# Telescope_Interface_shield.net
KiCad netlist of a schematic drawn in EAGLE
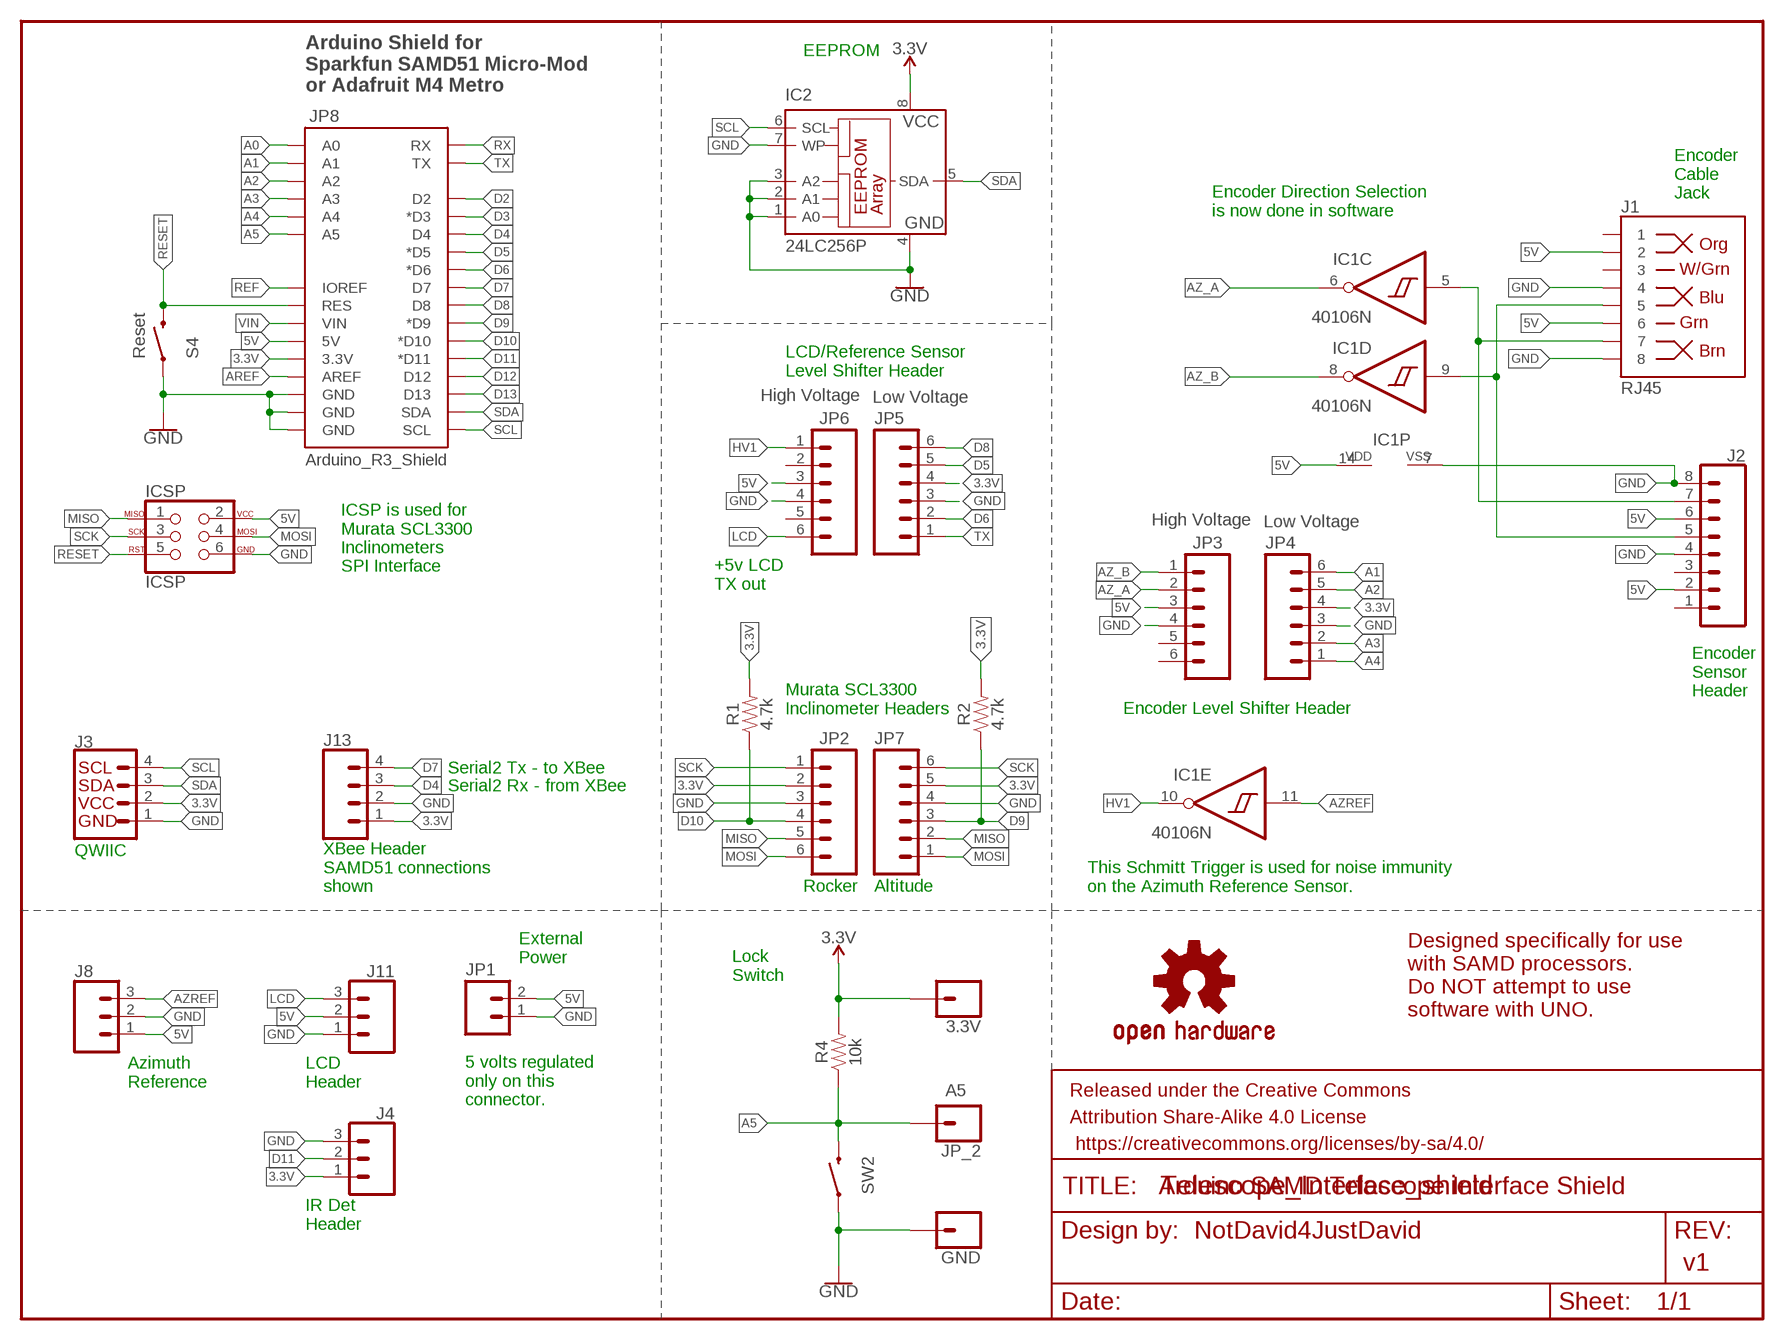
[diagram p0: schematic, sheet 1]

(export (version "E")
  (design (tool "Eeschema 10.0.6"))
  (components
    (comp (ref "3.3V")
      (value "CONN_01")
      (footprint "eagle-import:1X01")
      (libsource (lib "eagle-import") (part "CONN_01"))
    )
    (comp (ref "FRAME1")
      (value "FRAME-LETTER")
      (footprint "eagle-import:CREATIVE_COMMONS")
      (fields (field (name "DESIGNER") "NotDavid4JustDavid") (field (name "REV") "v1"))
      (libsource (lib "eagle-import") (part "FRAME-LETTER"))
    )
    (comp (ref "GND")
      (value "CONN_01")
      (footprint "eagle-import:1X01")
      (libsource (lib "eagle-import") (part "CONN_01"))
    )
    (comp (ref "IC1")
      (value "40106N")
      (footprint "eagle-import:DIL14")
      (libsource (lib "eagle-import") (part "40106N"))
    )
    (comp (ref "IC2")
      (value "24LC256P")
      (footprint "eagle-import:DIL8")
      (fields (field (name "MF") "MICROCHIP") (field (name "MPN") "24LC256-E/P"))
      (libsource (lib "eagle-import") (part "24PLC256"))
    )
    (comp (ref "ICSP")
      (value "ICSP")
      (footprint "eagle-import:2X3")
      (libsource (lib "eagle-import") (part "AVR_SPI_PROG_3X2PTH"))
    )
    (comp (ref "J1")
      (value "RJ45")
      (footprint "eagle-import:RJ45-8")
      (libsource (lib "eagle-import") (part "RJ45-8"))
    )
    (comp (ref "J2")
      (value "CONN_08\"")
      (footprint "eagle-import:1X08")
      (libsource (lib "eagle-import") (part "CONN_08{dblquote}"))
    )
    (comp (ref "J3")
      (value "QWIIC_CONNECTORJS-1MM")
      (footprint "eagle-import:JST04_1MM_RA")
      (libsource (lib "eagle-import") (part "QWIIC_CONNECTORJS-1MM"))
    )
    (comp (ref "J4")
      (value "455-1750-1-ND")
      (footprint "eagle-import:1X03")
      (libsource (lib "eagle-import") (part "CONN_03"))
    )
    (comp (ref "J8")
      (value "455-1750-1-ND")
      (footprint "eagle-import:1X03")
      (libsource (lib "eagle-import") (part "CONN_03"))
    )
    (comp (ref "J11")
      (value "455-1750-1-ND")
      (footprint "eagle-import:1X03")
      (libsource (lib "eagle-import") (part "CONN_03"))
    )
    (comp (ref "J13")
      (value "CONN_04PTH")
      (footprint "eagle-import:1X04")
      (libsource (lib "eagle-import") (part "CONN_04PTH"))
    )
    (comp (ref "JP1")
      (value "CONN_02JST-PTH-2")
      (footprint "eagle-import:JST-2-PTH")
      (libsource (lib "eagle-import") (part "CONN_02JST-PTH-2"))
    )
    (comp (ref "JP2")
      (value "M06SIP")
      (footprint "eagle-import:1X06")
      (libsource (lib "eagle-import") (part "M06SIP"))
    )
    (comp (ref "JP3")
      (value "M06SIP")
      (footprint "eagle-import:1X06")
      (libsource (lib "eagle-import") (part "M06SIP"))
    )
    (comp (ref "JP4")
      (value "M06SIP")
      (footprint "eagle-import:1X06")
      (libsource (lib "eagle-import") (part "M06SIP"))
    )
    (comp (ref "JP5")
      (value "M06SIP")
      (footprint "eagle-import:1X06")
      (libsource (lib "eagle-import") (part "M06SIP"))
    )
    (comp (ref "JP6")
      (value "M06SIP")
      (footprint "eagle-import:1X06")
      (libsource (lib "eagle-import") (part "M06SIP"))
    )
    (comp (ref "JP7")
      (value "M06SIP")
      (footprint "eagle-import:1X06")
      (libsource (lib "eagle-import") (part "M06SIP"))
    )
    (comp (ref "JP8")
      (value "ARDUINO_R3_SHIELDR3_PROTO_SHIELD")
      (footprint "eagle-import:UNO_R3_PROTO_SHIELD")
      (libsource (lib "eagle-import") (part "ARDUINO_R3_SHIELDR3_PROTO_SHIELD"))
    )
    (comp (ref "JP_2")
      (value "CONN_01")
      (footprint "eagle-import:1X01")
      (libsource (lib "eagle-import") (part "CONN_01"))
    )
    (comp (ref "LOGO1")
      (value "OSHW-LOGOS")
      (footprint "eagle-import:OSHW-LOGO-S")
      (libsource (lib "eagle-import") (part "OSHW-LOGOS"))
    )
    (comp (ref "R1")
      (value "4.7k")
      (footprint "eagle-import:0603")
      (libsource (lib "eagle-import") (part "4.7KOHM-0603-1/10W-1%"))
    )
    (comp (ref "R2")
      (value "4.7k")
      (footprint "eagle-import:0603")
      (libsource (lib "eagle-import") (part "4.7KOHM-0603-1/10W-1%"))
    )
    (comp (ref "R4")
      (value "10k")
      (footprint "eagle-import:AXIAL-0.3")
      (libsource (lib "eagle-import") (part "10KOHM-HORIZ-1/4W-5%"))
    )
    (comp (ref "S4")
      (value "MOMENTARY-SWITCH-SPST-PTH-6.0MM")
      (footprint "eagle-import:TACTILE_SWITCH_PTH_6.0MM")
      (libsource (lib "eagle-import") (part "MOMENTARY-SWITCH-SPST-PTH-6.0MM"))
    )
    (comp (ref "SW2")
      (value "MOMENTARY-SWITCH-SPST-PTH-6.0MM")
      (footprint "eagle-import:TACTILE_SWITCH_PTH_6.0MM")
      (libsource (lib "eagle-import") (part "MOMENTARY-SWITCH-SPST-PTH-6.0MM"))
    )
  )
  (nets
    (net (code "1") (name "3.3V") (class "Default")
      (node (ref "3.3V") (pin "1") (pinfunction "1_1") (pintype "passive"))
      (node (ref "IC2") (pin "8") (pinfunction "VCC_8") (pintype "power_in"))
      (node (ref "J13") (pin "1") (pinfunction "1_1") (pintype "passive"))
      (node (ref "J3") (pin "2") (pinfunction "2_2") (pintype "power_in"))
      (node (ref "J4") (pin "1") (pinfunction "1_1") (pintype "passive"))
      (node (ref "JP2") (pin "2") (pinfunction "2_2") (pintype "passive"))
      (node (ref "JP4") (pin "4") (pinfunction "4_4") (pintype "passive"))
      (node (ref "JP5") (pin "4") (pinfunction "4_4") (pintype "passive"))
      (node (ref "JP7") (pin "5") (pinfunction "5_5") (pintype "passive"))
      (node (ref "JP8") (pin "3.3V") (pinfunction "3.3V_3.3V") (pintype "bidirectional"))
      (node (ref "R1") (pin "2") (pinfunction "2_2") (pintype "passive"))
      (node (ref "R2") (pin "2") (pinfunction "2_2") (pintype "passive"))
      (node (ref "R4") (pin "P$2") (pinfunction "2_P$2") (pintype "passive"))
    )
    (net (code "2") (name "5V") (class "Default")
      (node (ref "IC1") (pin "14") (pinfunction "VDD_14") (pintype "power_in"))
      (node (ref "ICSP") (pin "2") (pinfunction "2_2") (pintype "passive"))
      (node (ref "J1") (pin "2") (pinfunction "2_2") (pintype "bidirectional"))
      (node (ref "J1") (pin "6") (pinfunction "6_6") (pintype "bidirectional"))
      (node (ref "J11") (pin "2") (pinfunction "2_2") (pintype "passive"))
      (node (ref "J2") (pin "2") (pinfunction "2_2") (pintype "passive"))
      (node (ref "J2") (pin "6") (pinfunction "6_6") (pintype "passive"))
      (node (ref "J8") (pin "1") (pinfunction "1_1") (pintype "passive"))
      (node (ref "JP1") (pin "2") (pinfunction "2_2") (pintype "passive"))
      (node (ref "JP3") (pin "3") (pinfunction "3_3") (pintype "passive"))
      (node (ref "JP6") (pin "3") (pinfunction "3_3") (pintype "passive"))
      (node (ref "JP8") (pin "5V") (pinfunction "5V_5V") (pintype "bidirectional"))
    )
    (net (code "3") (name "A0") (class "Default")
      (node (ref "JP8") (pin "A0") (pinfunction "A0_A0") (pintype "bidirectional"))
    )
    (net (code "4") (name "A1") (class "Default")
      (node (ref "JP4") (pin "6") (pinfunction "6_6") (pintype "passive"))
      (node (ref "JP8") (pin "A1") (pinfunction "A1_A1") (pintype "bidirectional"))
    )
    (net (code "5") (name "A2") (class "Default")
      (node (ref "JP4") (pin "5") (pinfunction "5_5") (pintype "passive"))
      (node (ref "JP8") (pin "A2") (pinfunction "A2_A2") (pintype "bidirectional"))
    )
    (net (code "6") (name "A3") (class "Default")
      (node (ref "JP4") (pin "2") (pinfunction "2_2") (pintype "passive"))
      (node (ref "JP8") (pin "A3") (pinfunction "A3_A3") (pintype "bidirectional"))
    )
    (net (code "7") (name "A4") (class "Default")
      (node (ref "JP4") (pin "1") (pinfunction "1_1") (pintype "passive"))
      (node (ref "JP8") (pin "A4") (pinfunction "A4_A4") (pintype "bidirectional"))
    )
    (net (code "8") (name "A5") (class "Default")
      (node (ref "JP8") (pin "A5") (pinfunction "A5_A5") (pintype "bidirectional"))
      (node (ref "JP_2") (pin "1") (pinfunction "1_1") (pintype "passive"))
      (node (ref "R4") (pin "P$1") (pinfunction "1_P$1") (pintype "passive"))
      (node (ref "SW2") (pin "3") (pinfunction "2_3") (pintype "passive"))
    )
    (net (code "9") (name "AREF") (class "Default")
      (node (ref "JP8") (pin "AREF") (pinfunction "AREF_AREF") (pintype "bidirectional"))
    )
    (net (code "10") (name "AZREF") (class "Default")
      (node (ref "IC1") (pin "11") (pinfunction "I_11") (pintype "input"))
      (node (ref "J8") (pin "3") (pinfunction "3_3") (pintype "passive"))
    )
    (net (code "11") (name "AZ_A") (class "Default")
      (node (ref "IC1") (pin "6") (pinfunction "O_6") (pintype "output"))
      (node (ref "JP3") (pin "2") (pinfunction "2_2") (pintype "passive"))
    )
    (net (code "12") (name "AZ_B") (class "Default")
      (node (ref "IC1") (pin "8") (pinfunction "O_8") (pintype "output"))
      (node (ref "JP3") (pin "1") (pinfunction "1_1") (pintype "passive"))
    )
    (net (code "13") (name "D2") (class "Default")
      (node (ref "JP8") (pin "D2") (pinfunction "D2_D2") (pintype "bidirectional"))
    )
    (net (code "14") (name "D3") (class "Default")
      (node (ref "JP8") (pin "D3") (pinfunction "*D3_D3") (pintype "bidirectional"))
    )
    (net (code "15") (name "D4") (class "Default")
      (node (ref "J13") (pin "3") (pinfunction "3_3") (pintype "passive"))
      (node (ref "JP8") (pin "D4") (pinfunction "D4_D4") (pintype "bidirectional"))
    )
    (net (code "16") (name "D5") (class "Default")
      (node (ref "JP5") (pin "5") (pinfunction "5_5") (pintype "passive"))
      (node (ref "JP8") (pin "D5") (pinfunction "*D5_D5") (pintype "bidirectional"))
    )
    (net (code "17") (name "D6") (class "Default")
      (node (ref "JP5") (pin "2") (pinfunction "2_2") (pintype "passive"))
      (node (ref "JP8") (pin "D6") (pinfunction "*D6_D6") (pintype "bidirectional"))
    )
    (net (code "18") (name "D7") (class "Default")
      (node (ref "J13") (pin "4") (pinfunction "4_4") (pintype "passive"))
      (node (ref "JP8") (pin "D7") (pinfunction "D7_D7") (pintype "bidirectional"))
    )
    (net (code "19") (name "D8") (class "Default")
      (node (ref "JP5") (pin "6") (pinfunction "6_6") (pintype "passive"))
      (node (ref "JP8") (pin "D8") (pinfunction "D8_D8") (pintype "bidirectional"))
    )
    (net (code "20") (name "D9") (class "Default")
      (node (ref "JP7") (pin "3") (pinfunction "3_3") (pintype "passive"))
      (node (ref "JP8") (pin "D9") (pinfunction "*D9_D9") (pintype "bidirectional"))
      (node (ref "R2") (pin "1") (pinfunction "1_1") (pintype "passive"))
    )
    (net (code "21") (name "D10") (class "Default")
      (node (ref "JP2") (pin "4") (pinfunction "4_4") (pintype "passive"))
      (node (ref "JP8") (pin "D10") (pinfunction "*D10_D10") (pintype "bidirectional"))
      (node (ref "R1") (pin "1") (pinfunction "1_1") (pintype "passive"))
    )
    (net (code "22") (name "D11") (class "Default")
      (node (ref "J4") (pin "2") (pinfunction "2_2") (pintype "passive"))
      (node (ref "JP8") (pin "D11") (pinfunction "*D11_D11") (pintype "bidirectional"))
    )
    (net (code "23") (name "D12") (class "Default")
      (node (ref "JP8") (pin "D12") (pinfunction "D12_D12") (pintype "bidirectional"))
    )
    (net (code "24") (name "D13") (class "Default")
      (node (ref "JP8") (pin "D13") (pinfunction "D13_D13") (pintype "bidirectional"))
    )
    (net (code "25") (name "GND") (class "Default")
      (node (ref "GND") (pin "1") (pinfunction "1_1") (pintype "passive"))
      (node (ref "IC1") (pin "7") (pinfunction "VSS_7") (pintype "power_in"))
      (node (ref "IC2") (pin "1") (pinfunction "A0_1") (pintype "input"))
      (node (ref "IC2") (pin "2") (pinfunction "A1_2") (pintype "input"))
      (node (ref "IC2") (pin "3") (pinfunction "A2_3") (pintype "input"))
      (node (ref "IC2") (pin "4") (pinfunction "GND_4") (pintype "power_in"))
      (node (ref "IC2") (pin "7") (pinfunction "WP_7") (pintype "input"))
      (node (ref "ICSP") (pin "6") (pinfunction "6_6") (pintype "passive"))
      (node (ref "J1") (pin "4") (pinfunction "4_4") (pintype "bidirectional"))
      (node (ref "J1") (pin "8") (pinfunction "8_8") (pintype "bidirectional"))
      (node (ref "J11") (pin "1") (pinfunction "1_1") (pintype "passive"))
      (node (ref "J13") (pin "2") (pinfunction "2_2") (pintype "passive"))
      (node (ref "J2") (pin "4") (pinfunction "4_4") (pintype "passive"))
      (node (ref "J2") (pin "8") (pinfunction "8_8") (pintype "passive"))
      (node (ref "J3") (pin "1") (pinfunction "1_1") (pintype "power_in"))
      (node (ref "J4") (pin "3") (pinfunction "3_3") (pintype "passive"))
      (node (ref "J8") (pin "2") (pinfunction "2_2") (pintype "passive"))
      (node (ref "JP1") (pin "1") (pinfunction "1_1") (pintype "passive"))
      (node (ref "JP2") (pin "3") (pinfunction "3_3") (pintype "passive"))
      (node (ref "JP3") (pin "4") (pinfunction "4_4") (pintype "passive"))
      (node (ref "JP4") (pin "3") (pinfunction "3_3") (pintype "passive"))
      (node (ref "JP5") (pin "3") (pinfunction "3_3") (pintype "passive"))
      (node (ref "JP6") (pin "4") (pinfunction "4_4") (pintype "passive"))
      (node (ref "JP7") (pin "4") (pinfunction "4_4") (pintype "passive"))
      (node (ref "JP8") (pin "GND@0") (pinfunction "GND_GND@0") (pintype "bidirectional"))
      (node (ref "JP8") (pin "GND@1") (pinfunction "GND_GND@1") (pintype "bidirectional"))
      (node (ref "JP8") (pin "GND@2") (pinfunction "GND_GND@2") (pintype "bidirectional"))
      (node (ref "S4") (pin "1") (pinfunction "1_1") (pintype "passive"))
      (node (ref "SW2") (pin "1") (pinfunction "1_1") (pintype "passive"))
    )
    (net (code "26") (name "HV1") (class "Default")
      (node (ref "IC1") (pin "10") (pinfunction "O_10") (pintype "output"))
      (node (ref "JP6") (pin "1") (pinfunction "1_1") (pintype "passive"))
    )
    (net (code "27") (name "LCD") (class "Default")
      (node (ref "J11") (pin "3") (pinfunction "3_3") (pintype "passive"))
      (node (ref "JP6") (pin "6") (pinfunction "6_6") (pintype "passive"))
    )
    (net (code "28") (name "MISO") (class "Default")
      (node (ref "ICSP") (pin "1") (pinfunction "1_1") (pintype "passive"))
      (node (ref "JP2") (pin "5") (pinfunction "5_5") (pintype "passive"))
      (node (ref "JP7") (pin "2") (pinfunction "2_2") (pintype "passive"))
    )
    (net (code "29") (name "MOSI") (class "Default")
      (node (ref "ICSP") (pin "4") (pinfunction "4_4") (pintype "passive"))
      (node (ref "JP2") (pin "6") (pinfunction "6_6") (pintype "passive"))
      (node (ref "JP7") (pin "1") (pinfunction "1_1") (pintype "passive"))
    )
    (net (code "30") (name "Net-(IC1C-I)") (class "Default")
      (node (ref "IC1") (pin "5") (pinfunction "I_5") (pintype "input"))
      (node (ref "J1") (pin "7") (pinfunction "7_7") (pintype "bidirectional"))
      (node (ref "J2") (pin "7") (pinfunction "7_7") (pintype "passive"))
    )
    (net (code "31") (name "Net-(IC1D-I)") (class "Default")
      (node (ref "IC1") (pin "9") (pinfunction "I_9") (pintype "input"))
      (node (ref "J1") (pin "5") (pinfunction "5_5") (pintype "bidirectional"))
      (node (ref "J2") (pin "5") (pinfunction "5_5") (pintype "passive"))
    )
    (net (code "32") (name "REF") (class "Default")
      (node (ref "JP8") (pin "IOREF") (pinfunction "IOREF_IOREF") (pintype "bidirectional"))
    )
    (net (code "33") (name "RESET") (class "Default")
      (node (ref "JP8") (pin "RES") (pinfunction "RES_RES") (pintype "bidirectional"))
      (node (ref "S4") (pin "3") (pinfunction "2_3") (pintype "passive"))
    )
    (net (code "34") (name "RX") (class "Default")
      (node (ref "JP8") (pin "RX") (pinfunction "RX_RX") (pintype "bidirectional"))
    )
    (net (code "35") (name "SCK") (class "Default")
      (node (ref "ICSP") (pin "3") (pinfunction "3_3") (pintype "passive"))
      (node (ref "JP2") (pin "1") (pinfunction "1_1") (pintype "passive"))
      (node (ref "JP7") (pin "6") (pinfunction "6_6") (pintype "passive"))
    )
    (net (code "36") (name "SCL") (class "Default")
      (node (ref "IC2") (pin "6") (pinfunction "SCL_6") (pintype "input"))
      (node (ref "J3") (pin "4") (pinfunction "4_4") (pintype "passive"))
      (node (ref "JP8") (pin "SCL") (pinfunction "SCL_SCL") (pintype "bidirectional"))
    )
    (net (code "37") (name "SDA") (class "Default")
      (node (ref "IC2") (pin "5") (pinfunction "SDA_5") (pintype "bidirectional"))
      (node (ref "J3") (pin "3") (pinfunction "3_3") (pintype "passive"))
      (node (ref "JP8") (pin "SDA") (pinfunction "SDA_SDA") (pintype "bidirectional"))
    )
    (net (code "38") (name "TX") (class "Default")
      (node (ref "JP5") (pin "1") (pinfunction "1_1") (pintype "passive"))
      (node (ref "JP8") (pin "TX") (pinfunction "TX_TX") (pintype "bidirectional"))
    )
    (net (code "39") (name "VIN") (class "Default")
      (node (ref "JP8") (pin "VIN") (pinfunction "VIN_VIN") (pintype "bidirectional"))
    )
    (net (code "40") (name "unconnected-(ICSP-Pad5)") (class "Default")
      (node (ref "ICSP") (pin "5") (pinfunction "5_5") (pintype "passive"))
    )
    (net (code "41") (name "unconnected-(J1-Pad1)") (class "Default")
      (node (ref "J1") (pin "1") (pinfunction "1_1") (pintype "bidirectional"))
    )
    (net (code "42") (name "unconnected-(J1-Pad3)") (class "Default")
      (node (ref "J1") (pin "3") (pinfunction "3_3") (pintype "bidirectional"))
    )
    (net (code "43") (name "unconnected-(J2-Pad1)") (class "Default")
      (node (ref "J2") (pin "1") (pinfunction "1_1") (pintype "passive"))
    )
    (net (code "44") (name "unconnected-(J2-Pad3)") (class "Default")
      (node (ref "J2") (pin "3") (pinfunction "3_3") (pintype "passive"))
    )
    (net (code "45") (name "unconnected-(JP3-Pad5)") (class "Default")
      (node (ref "JP3") (pin "5") (pinfunction "5_5") (pintype "passive"))
    )
    (net (code "46") (name "unconnected-(JP3-Pad6)") (class "Default")
      (node (ref "JP3") (pin "6") (pinfunction "6_6") (pintype "passive"))
    )
    (net (code "47") (name "unconnected-(JP6-Pad2)") (class "Default")
      (node (ref "JP6") (pin "2") (pinfunction "2_2") (pintype "passive"))
    )
    (net (code "48") (name "unconnected-(JP6-Pad5)") (class "Default")
      (node (ref "JP6") (pin "5") (pinfunction "5_5") (pintype "passive"))
    )
  )
)
